# Roseta_AC.net
KiCad netlist of a schematic drawn in Altium Designer
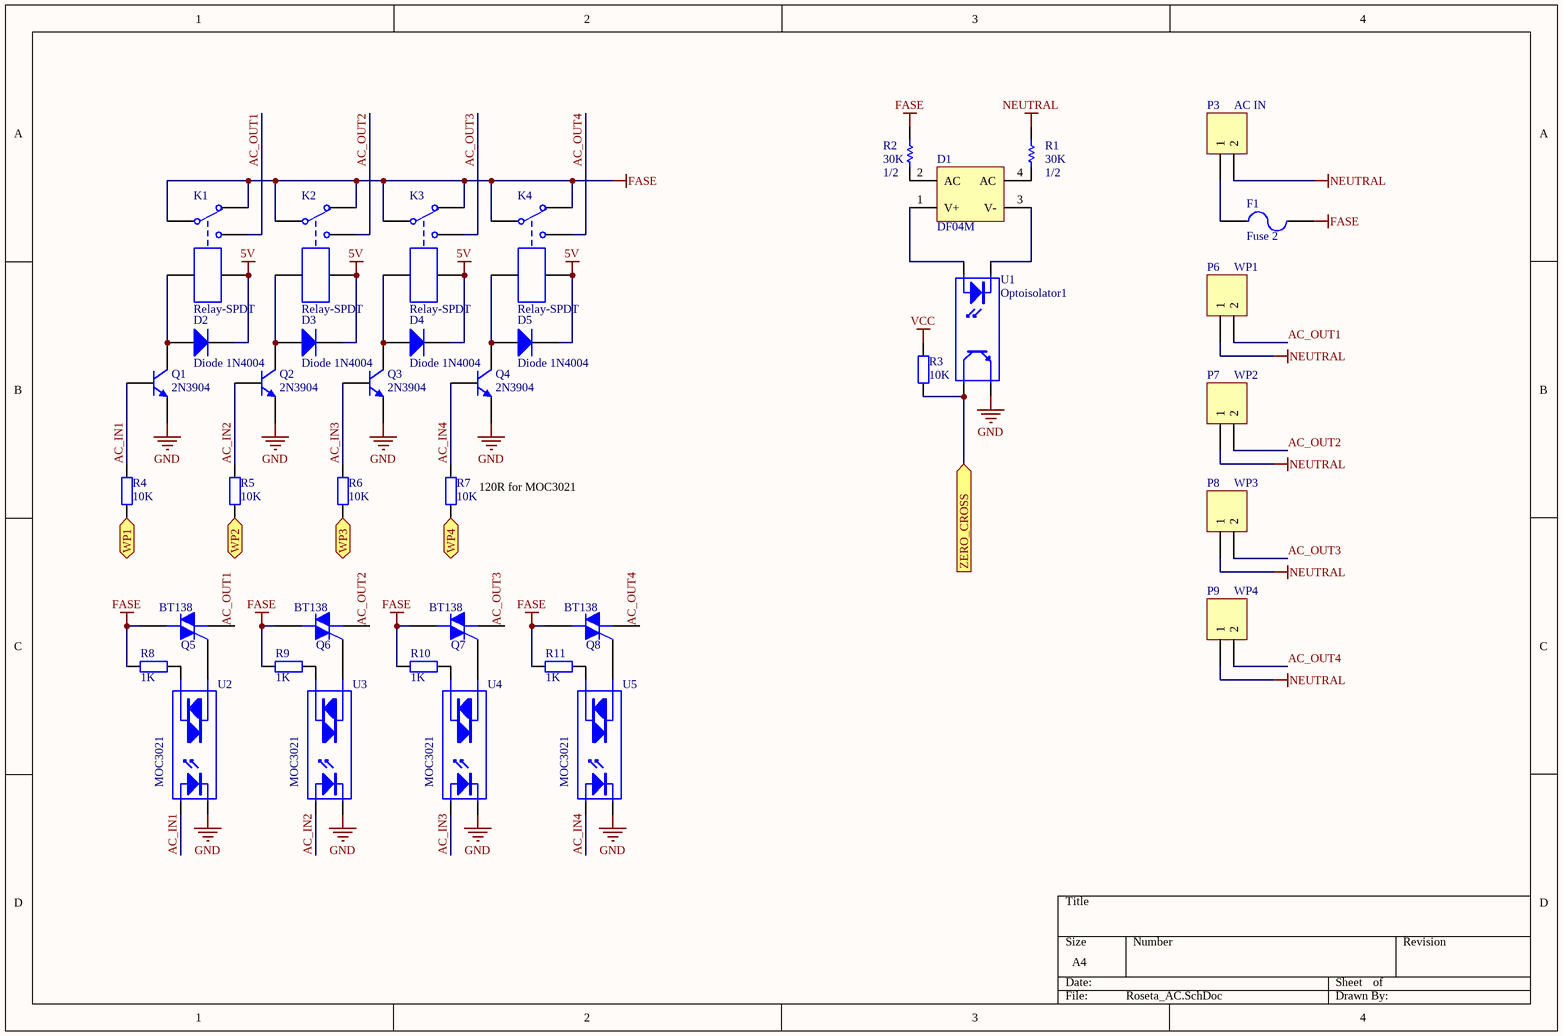
[diagram p0: Roseta_AC.SchDoc]

(export (version "E")
  (design (tool "Eeschema 10.0.6"))
  (components
    (comp (ref "D1")
      (value "DF04M")
      (footprint "DF04M")
      (description "Diode Bridge")
      (fields (field (name "PUBLISHER") "Altium Limited"))
      (libsource (lib "Miscellaneous Devices") (part "Bridge2"))
    )
    (comp (ref "D2")
      (value "Diode 1N4004")
      (footprint "1n4007")
      (description "1 Amp General Purpose Rectifier")
      (fields (field (name "PUBLISHER") "Altium Limited"))
      (libsource (lib "Miscellaneous Devices") (part "Diode 1N4004"))
    )
    (comp (ref "D3")
      (value "Diode 1N4004")
      (footprint "1n4007")
      (description "1 Amp General Purpose Rectifier")
      (fields (field (name "PUBLISHER") "Altium Limited"))
      (libsource (lib "Miscellaneous Devices") (part "Diode 1N4004"))
    )
    (comp (ref "D4")
      (value "Diode 1N4004")
      (footprint "1n4007")
      (description "1 Amp General Purpose Rectifier")
      (fields (field (name "PUBLISHER") "Altium Limited"))
      (libsource (lib "Miscellaneous Devices") (part "Diode 1N4004"))
    )
    (comp (ref "D5")
      (value "Diode 1N4004")
      (footprint "1n4007")
      (description "1 Amp General Purpose Rectifier")
      (fields (field (name "PUBLISHER") "Altium Limited"))
      (libsource (lib "Miscellaneous Devices") (part "Diode 1N4004"))
    )
    (comp (ref "F1")
      (value "Fuse 2")
      (footprint "PIN-W2/E2.8")
      (description "Fuse")
      (fields (field (name "PUBLISHER") "Altium Limited"))
      (libsource (lib "Miscellaneous Devices") (part "Fuse 2"))
    )
    (comp (ref "K1")
      (value "Relay-SPDT")
      (footprint "RELAY-HRS4")
      (description "Single-Pole Dual-Throw Relay")
      (fields (field (name "PUBLISHER") "Altium Limited"))
      (libsource (lib "Miscellaneous Devices") (part "Relay-SPDT"))
    )
    (comp (ref "K2")
      (value "Relay-SPDT")
      (footprint "RELAY-HRS4")
      (description "Single-Pole Dual-Throw Relay")
      (fields (field (name "PUBLISHER") "Altium Limited"))
      (libsource (lib "Miscellaneous Devices") (part "Relay-SPDT"))
    )
    (comp (ref "K3")
      (value "Relay-SPDT")
      (footprint "RELAY-HRS4")
      (description "Single-Pole Dual-Throw Relay")
      (fields (field (name "PUBLISHER") "Altium Limited"))
      (libsource (lib "Miscellaneous Devices") (part "Relay-SPDT"))
    )
    (comp (ref "K4")
      (value "Relay-SPDT")
      (footprint "RELAY-HRS4")
      (description "Single-Pole Dual-Throw Relay")
      (fields (field (name "PUBLISHER") "Altium Limited"))
      (libsource (lib "Miscellaneous Devices") (part "Relay-SPDT"))
    )
    (comp (ref "P3")
      (value "AC IN")
      (footprint "TERMINAL BLOCK X2")
      (description "Header, 2-Pin")
      (fields (field (name "PUBLISHER") "Altium Limited"))
      (libsource (lib "Miscellaneous Connectors") (part "Header 2"))
    )
    (comp (ref "P6")
      (value "WP1")
      (footprint "TERMINAL BLOCK X2")
      (description "Header, 2-Pin")
      (fields (field (name "PUBLISHER") "Altium Limited"))
      (libsource (lib "Miscellaneous Connectors") (part "Header 2"))
    )
    (comp (ref "P7")
      (value "WP2")
      (footprint "TERMINAL BLOCK X2")
      (description "Header, 2-Pin")
      (fields (field (name "PUBLISHER") "Altium Limited"))
      (libsource (lib "Miscellaneous Connectors") (part "Header 2"))
    )
    (comp (ref "P8")
      (value "WP3")
      (footprint "TERMINAL BLOCK X2")
      (description "Header, 2-Pin")
      (fields (field (name "PUBLISHER") "Altium Limited"))
      (libsource (lib "Miscellaneous Connectors") (part "Header 2"))
    )
    (comp (ref "P9")
      (value "WP4")
      (footprint "TERMINAL BLOCK X2")
      (description "Header, 2-Pin")
      (fields (field (name "PUBLISHER") "Altium Limited"))
      (libsource (lib "Miscellaneous Connectors") (part "Header 2"))
    )
    (comp (ref "Q1")
      (value "2N3904")
      (footprint "BCY-W3/E4")
      (description "NPN General Purpose Amplifier")
      (fields (field (name "PUBLISHER") "Altium Limited"))
      (libsource (lib "Miscellaneous Devices") (part "2N3904"))
    )
    (comp (ref "Q2")
      (value "2N3904")
      (footprint "BCY-W3/E4")
      (description "NPN General Purpose Amplifier")
      (fields (field (name "PUBLISHER") "Altium Limited"))
      (libsource (lib "Miscellaneous Devices") (part "2N3904"))
    )
    (comp (ref "Q3")
      (value "2N3904")
      (footprint "BCY-W3/E4")
      (description "NPN General Purpose Amplifier")
      (fields (field (name "PUBLISHER") "Altium Limited"))
      (libsource (lib "Miscellaneous Devices") (part "2N3904"))
    )
    (comp (ref "Q4")
      (value "2N3904")
      (footprint "BCY-W3/E4")
      (description "NPN General Purpose Amplifier")
      (fields (field (name "PUBLISHER") "Altium Limited"))
      (libsource (lib "Miscellaneous Devices") (part "2N3904"))
    )
    (comp (ref "Q5")
      (value "BT138")
      (footprint "221A-09")
      (description "Silicon Bidirectional Triode Thyristor")
      (fields (field (name "PUBLISHER") "Altium Limited"))
      (libsource (lib "Motorola Discrete TRIAC") (part "MAC15A6"))
    )
    (comp (ref "Q6")
      (value "BT138")
      (footprint "221A-09")
      (description "Silicon Bidirectional Triode Thyristor")
      (fields (field (name "PUBLISHER") "Altium Limited"))
      (libsource (lib "Motorola Discrete TRIAC") (part "MAC15A6"))
    )
    (comp (ref "Q7")
      (value "BT138")
      (footprint "221A-09")
      (description "Silicon Bidirectional Triode Thyristor")
      (fields (field (name "PUBLISHER") "Altium Limited"))
      (libsource (lib "Motorola Discrete TRIAC") (part "MAC15A6"))
    )
    (comp (ref "Q8")
      (value "BT138")
      (footprint "221A-09")
      (description "Silicon Bidirectional Triode Thyristor")
      (fields (field (name "PUBLISHER") "Altium Limited"))
      (libsource (lib "Motorola Discrete TRIAC") (part "MAC15A6"))
    )
    (comp (ref "R1")
      (value "1/2")
      (footprint "AXIAL-0.3")
      (description "Resistor")
      (fields (field (name "ALTIUM_VALUE") "30K") (field (name "PUBLISHER") "Altium Limited"))
      (libsource (lib "Miscellaneous Devices") (part "Res1"))
    )
    (comp (ref "R2")
      (value "1/2")
      (footprint "AXIAL-0.3")
      (description "Resistor")
      (fields (field (name "ALTIUM_VALUE") "30K") (field (name "PUBLISHER") "Altium Limited"))
      (libsource (lib "Miscellaneous Devices") (part "Res1"))
    )
    (comp (ref "R3")
      (value "10K")
      (footprint "1608[0603]")
      (description "Resistor")
      (fields (field (name "Comment") "Res2") (field (name "PUBLISHER") "Altium Limited"))
      (libsource (lib "") (part "Res2_2"))
    )
    (comp (ref "R4")
      (value "10K")
      (footprint "1608[0603]")
      (description "Resistor")
      (fields (field (name "Comment") "Res2") (field (name "PUBLISHER") "Altium Limited"))
      (libsource (lib "") (part "Res2_1"))
    )
    (comp (ref "R5")
      (value "10K")
      (footprint "1608[0603]")
      (description "Resistor")
      (fields (field (name "Comment") "Res2") (field (name "PUBLISHER") "Altium Limited"))
      (libsource (lib "") (part "Res2_1"))
    )
    (comp (ref "R6")
      (value "10K")
      (footprint "1608[0603]")
      (description "Resistor")
      (fields (field (name "Comment") "Res2") (field (name "PUBLISHER") "Altium Limited"))
      (libsource (lib "") (part "Res2_1"))
    )
    (comp (ref "R7")
      (value "10K")
      (footprint "1608[0603]")
      (description "Resistor")
      (fields (field (name "Comment") "Res2") (field (name "PUBLISHER") "Altium Limited"))
      (libsource (lib "") (part "Res2_1"))
    )
    (comp (ref "R8")
      (value "1K")
      (footprint "1608[0603]")
      (description "Resistor")
      (fields (field (name "Comment") "Res2") (field (name "PUBLISHER") "Altium Limited"))
      (libsource (lib "Miscellaneous Devices") (part "Res2"))
    )
    (comp (ref "R9")
      (value "1K")
      (footprint "1608[0603]")
      (description "Resistor")
      (fields (field (name "Comment") "Res2") (field (name "PUBLISHER") "Altium Limited"))
      (libsource (lib "Miscellaneous Devices") (part "Res2"))
    )
    (comp (ref "R10")
      (value "1K")
      (footprint "1608[0603]")
      (description "Resistor")
      (fields (field (name "Comment") "Res2") (field (name "PUBLISHER") "Altium Limited"))
      (libsource (lib "Miscellaneous Devices") (part "Res2"))
    )
    (comp (ref "R11")
      (value "1K")
      (footprint "1608[0603]")
      (description "Resistor")
      (fields (field (name "Comment") "Res2") (field (name "PUBLISHER") "Altium Limited"))
      (libsource (lib "Miscellaneous Devices") (part "Res2"))
    )
    (comp (ref "U1")
      (value "Optoisolator1")
      (footprint "DIP-6")
      (description "4-Pin Phototransistor Optocoupler")
      (fields (field (name "PUBLISHER") "Altium Limited"))
      (libsource (lib "Miscellaneous Devices") (part "Optoisolator1"))
    )
    (comp (ref "U2")
      (value "MOC3021")
      (footprint "DIP-6")
      (description "Opto-Triac")
      (fields (field (name "PUBLISHER") "Altium Limited"))
      (libsource (lib "Miscellaneous Devices") (part "Opto TRIAC"))
    )
    (comp (ref "U3")
      (value "MOC3021")
      (footprint "DIP-6")
      (description "Opto-Triac")
      (fields (field (name "PUBLISHER") "Altium Limited"))
      (libsource (lib "Miscellaneous Devices") (part "Opto TRIAC"))
    )
    (comp (ref "U4")
      (value "MOC3021")
      (footprint "DIP-6")
      (description "Opto-Triac")
      (fields (field (name "PUBLISHER") "Altium Limited"))
      (libsource (lib "Miscellaneous Devices") (part "Opto TRIAC"))
    )
    (comp (ref "U5")
      (value "MOC3021")
      (footprint "DIP-6")
      (description "Opto-Triac")
      (fields (field (name "PUBLISHER") "Altium Limited"))
      (libsource (lib "Miscellaneous Devices") (part "Opto TRIAC"))
    )
  )
  (nets
    (net (code "1") (name "/AC_IN1") (class "Default")
      (node (ref "Q1") (pin "2") (pinfunction "B_2") (pintype "passive"))
      (node (ref "R4") (pin "2") (pinfunction "2_2") (pintype "passive"))
      (node (ref "U2") (pin "1") (pinfunction "A_1") (pintype "passive"))
    )
    (net (code "2") (name "/AC_IN2") (class "Default")
      (node (ref "Q2") (pin "2") (pinfunction "B_2") (pintype "passive"))
      (node (ref "R5") (pin "2") (pinfunction "2_2") (pintype "passive"))
      (node (ref "U3") (pin "1") (pinfunction "A_1") (pintype "passive"))
    )
    (net (code "3") (name "/AC_IN3") (class "Default")
      (node (ref "Q3") (pin "2") (pinfunction "B_2") (pintype "passive"))
      (node (ref "R6") (pin "2") (pinfunction "2_2") (pintype "passive"))
      (node (ref "U4") (pin "1") (pinfunction "A_1") (pintype "passive"))
    )
    (net (code "4") (name "/AC_IN4") (class "Default")
      (node (ref "Q4") (pin "2") (pinfunction "B_2") (pintype "passive"))
      (node (ref "R7") (pin "2") (pinfunction "2_2") (pintype "passive"))
      (node (ref "U5") (pin "1") (pinfunction "A_1") (pintype "passive"))
    )
    (net (code "5") (name "/AC_OUT1") (class "Default")
      (node (ref "K1") (pin "3") (pinfunction "3_3") (pintype "passive"))
      (node (ref "P6") (pin "2") (pinfunction "2_2") (pintype "passive"))
      (node (ref "Q5") (pin "1") (pinfunction "M1_1") (pintype "passive"))
    )
    (net (code "6") (name "/AC_OUT2") (class "Default")
      (node (ref "K2") (pin "3") (pinfunction "3_3") (pintype "passive"))
      (node (ref "P7") (pin "2") (pinfunction "2_2") (pintype "passive"))
      (node (ref "Q6") (pin "1") (pinfunction "M1_1") (pintype "passive"))
    )
    (net (code "7") (name "/AC_OUT3") (class "Default")
      (node (ref "K3") (pin "3") (pinfunction "3_3") (pintype "passive"))
      (node (ref "P8") (pin "2") (pinfunction "2_2") (pintype "passive"))
      (node (ref "Q7") (pin "1") (pinfunction "M1_1") (pintype "passive"))
    )
    (net (code "8") (name "/AC_OUT4") (class "Default")
      (node (ref "K4") (pin "3") (pinfunction "3_3") (pintype "passive"))
      (node (ref "P9") (pin "2") (pinfunction "2_2") (pintype "passive"))
      (node (ref "Q8") (pin "1") (pinfunction "M1_1") (pintype "passive"))
    )
    (net (code "9") (name "/WP1") (class "Default")
      (node (ref "R4") (pin "1") (pinfunction "1_1") (pintype "passive"))
    )
    (net (code "10") (name "/WP2") (class "Default")
      (node (ref "R5") (pin "1") (pinfunction "1_1") (pintype "passive"))
    )
    (net (code "11") (name "/WP3") (class "Default")
      (node (ref "R6") (pin "1") (pinfunction "1_1") (pintype "passive"))
    )
    (net (code "12") (name "/WP4") (class "Default")
      (node (ref "R7") (pin "1") (pinfunction "1_1") (pintype "passive"))
    )
    (net (code "13") (name "/ZERO_CROSS") (class "Default")
      (node (ref "R3") (pin "2") (pinfunction "2_2") (pintype "passive"))
      (node (ref "U1") (pin "4") (pinfunction "C_4") (pintype "passive"))
    )
    (net (code "14") (name "5V") (class "Default")
      (node (ref "D2") (pin "2") (pinfunction "K_2") (pintype "passive"))
      (node (ref "D3") (pin "2") (pinfunction "K_2") (pintype "passive"))
      (node (ref "D4") (pin "2") (pinfunction "K_2") (pintype "passive"))
      (node (ref "D5") (pin "2") (pinfunction "K_2") (pintype "passive"))
      (node (ref "K1") (pin "5") (pinfunction "5_5") (pintype "passive"))
      (node (ref "K2") (pin "5") (pinfunction "5_5") (pintype "passive"))
      (node (ref "K3") (pin "5") (pinfunction "5_5") (pintype "passive"))
      (node (ref "K4") (pin "5") (pinfunction "5_5") (pintype "passive"))
    )
    (net (code "15") (name "FASE") (class "Default")
      (node (ref "F1") (pin "1") (pinfunction "1_1") (pintype "passive"))
      (node (ref "K1") (pin "1") (pinfunction "1_1") (pintype "passive"))
      (node (ref "K1") (pin "2") (pinfunction "2_2") (pintype "passive"))
      (node (ref "K2") (pin "1") (pinfunction "1_1") (pintype "passive"))
      (node (ref "K2") (pin "2") (pinfunction "2_2") (pintype "passive"))
      (node (ref "K3") (pin "1") (pinfunction "1_1") (pintype "passive"))
      (node (ref "K3") (pin "2") (pinfunction "2_2") (pintype "passive"))
      (node (ref "K4") (pin "1") (pinfunction "1_1") (pintype "passive"))
      (node (ref "K4") (pin "2") (pinfunction "2_2") (pintype "passive"))
      (node (ref "Q5") (pin "2") (pinfunction "M2_2") (pintype "passive"))
      (node (ref "Q6") (pin "2") (pinfunction "M2_2") (pintype "passive"))
      (node (ref "Q7") (pin "2") (pinfunction "M2_2") (pintype "passive"))
      (node (ref "Q8") (pin "2") (pinfunction "M2_2") (pintype "passive"))
      (node (ref "R10") (pin "2") (pinfunction "2_2") (pintype "passive"))
      (node (ref "R11") (pin "2") (pinfunction "2_2") (pintype "passive"))
      (node (ref "R2") (pin "2") (pinfunction "2_2") (pintype "passive"))
      (node (ref "R8") (pin "2") (pinfunction "2_2") (pintype "passive"))
      (node (ref "R9") (pin "2") (pinfunction "2_2") (pintype "passive"))
    )
    (net (code "16") (name "GND") (class "Default")
      (node (ref "Q1") (pin "1") (pinfunction "E_1") (pintype "passive"))
      (node (ref "Q2") (pin "1") (pinfunction "E_1") (pintype "passive"))
      (node (ref "Q3") (pin "1") (pinfunction "E_1") (pintype "passive"))
      (node (ref "Q4") (pin "1") (pinfunction "E_1") (pintype "passive"))
      (node (ref "U1") (pin "3") (pinfunction "E_3") (pintype "passive"))
      (node (ref "U2") (pin "2") (pinfunction "K_2") (pintype "passive"))
      (node (ref "U3") (pin "2") (pinfunction "K_2") (pintype "passive"))
      (node (ref "U4") (pin "2") (pinfunction "K_2") (pintype "passive"))
      (node (ref "U5") (pin "2") (pinfunction "K_2") (pintype "passive"))
    )
    (net (code "17") (name "NEUTRAL") (class "Default")
      (node (ref "P3") (pin "2") (pinfunction "2_2") (pintype "passive"))
      (node (ref "P6") (pin "1") (pinfunction "1_1") (pintype "passive"))
      (node (ref "P7") (pin "1") (pinfunction "1_1") (pintype "passive"))
      (node (ref "P8") (pin "1") (pinfunction "1_1") (pintype "passive"))
      (node (ref "P9") (pin "1") (pinfunction "1_1") (pintype "passive"))
      (node (ref "R1") (pin "2") (pinfunction "2_2") (pintype "passive"))
    )
    (net (code "18") (name "Net-(D1-AC-Pad2)") (class "Default")
      (node (ref "D1") (pin "2") (pinfunction "AC_2") (pintype "passive"))
      (node (ref "R2") (pin "1") (pinfunction "1_1") (pintype "passive"))
    )
    (net (code "19") (name "Net-(D1-AC-Pad4)") (class "Default")
      (node (ref "D1") (pin "4") (pinfunction "AC_4") (pintype "passive"))
      (node (ref "R1") (pin "1") (pinfunction "1_1") (pintype "passive"))
    )
    (net (code "20") (name "Net-(D1-V+)") (class "Default")
      (node (ref "D1") (pin "1") (pinfunction "V+_1") (pintype "passive"))
      (node (ref "U1") (pin "1") (pinfunction "A_1") (pintype "passive"))
    )
    (net (code "21") (name "Net-(D1-V-)") (class "Default")
      (node (ref "D1") (pin "3") (pinfunction "V-_3") (pintype "passive"))
      (node (ref "U1") (pin "2") (pinfunction "K_2") (pintype "passive"))
    )
    (net (code "22") (name "Net-(D2-A)") (class "Default")
      (node (ref "D2") (pin "1") (pinfunction "A_1") (pintype "passive"))
      (node (ref "K1") (pin "4") (pinfunction "4_4") (pintype "passive"))
      (node (ref "Q1") (pin "3") (pinfunction "C_3") (pintype "passive"))
    )
    (net (code "23") (name "Net-(D3-A)") (class "Default")
      (node (ref "D3") (pin "1") (pinfunction "A_1") (pintype "passive"))
      (node (ref "K2") (pin "4") (pinfunction "4_4") (pintype "passive"))
      (node (ref "Q2") (pin "3") (pinfunction "C_3") (pintype "passive"))
    )
    (net (code "24") (name "Net-(D4-A)") (class "Default")
      (node (ref "D4") (pin "1") (pinfunction "A_1") (pintype "passive"))
      (node (ref "K3") (pin "4") (pinfunction "4_4") (pintype "passive"))
      (node (ref "Q3") (pin "3") (pinfunction "C_3") (pintype "passive"))
    )
    (net (code "25") (name "Net-(D5-A)") (class "Default")
      (node (ref "D5") (pin "1") (pinfunction "A_1") (pintype "passive"))
      (node (ref "K4") (pin "4") (pinfunction "4_4") (pintype "passive"))
      (node (ref "Q4") (pin "3") (pinfunction "C_3") (pintype "passive"))
    )
    (net (code "26") (name "Net-(F1-Pad2)") (class "Default")
      (node (ref "F1") (pin "2") (pinfunction "2_2") (pintype "passive"))
      (node (ref "P3") (pin "1") (pinfunction "1_1") (pintype "passive"))
    )
    (net (code "27") (name "Net-(Q5-G)") (class "Default")
      (node (ref "Q5") (pin "3") (pinfunction "G_3") (pintype "passive"))
      (node (ref "U2") (pin "4") (pinfunction "A/K_4") (pintype "passive"))
    )
    (net (code "28") (name "Net-(Q6-G)") (class "Default")
      (node (ref "Q6") (pin "3") (pinfunction "G_3") (pintype "passive"))
      (node (ref "U3") (pin "4") (pinfunction "A/K_4") (pintype "passive"))
    )
    (net (code "29") (name "Net-(Q7-G)") (class "Default")
      (node (ref "Q7") (pin "3") (pinfunction "G_3") (pintype "passive"))
      (node (ref "U4") (pin "4") (pinfunction "A/K_4") (pintype "passive"))
    )
    (net (code "30") (name "Net-(Q8-G)") (class "Default")
      (node (ref "Q8") (pin "3") (pinfunction "G_3") (pintype "passive"))
      (node (ref "U5") (pin "4") (pinfunction "A/K_4") (pintype "passive"))
    )
    (net (code "31") (name "Net-(R8-Pad1)") (class "Default")
      (node (ref "R8") (pin "1") (pinfunction "1_1") (pintype "passive"))
      (node (ref "U2") (pin "3") (pinfunction "A/K_3") (pintype "passive"))
    )
    (net (code "32") (name "Net-(R9-Pad1)") (class "Default")
      (node (ref "R9") (pin "1") (pinfunction "1_1") (pintype "passive"))
      (node (ref "U3") (pin "3") (pinfunction "A/K_3") (pintype "passive"))
    )
    (net (code "33") (name "Net-(R10-Pad1)") (class "Default")
      (node (ref "R10") (pin "1") (pinfunction "1_1") (pintype "passive"))
      (node (ref "U4") (pin "3") (pinfunction "A/K_3") (pintype "passive"))
    )
    (net (code "34") (name "Net-(R11-Pad1)") (class "Default")
      (node (ref "R11") (pin "1") (pinfunction "1_1") (pintype "passive"))
      (node (ref "U5") (pin "3") (pinfunction "A/K_3") (pintype "passive"))
    )
    (net (code "35") (name "VCC") (class "Default")
      (node (ref "R3") (pin "1") (pinfunction "1_1") (pintype "passive"))
    )
  )
)
